# coracao.net
KiCad netlist of a schematic drawn in EAGLE
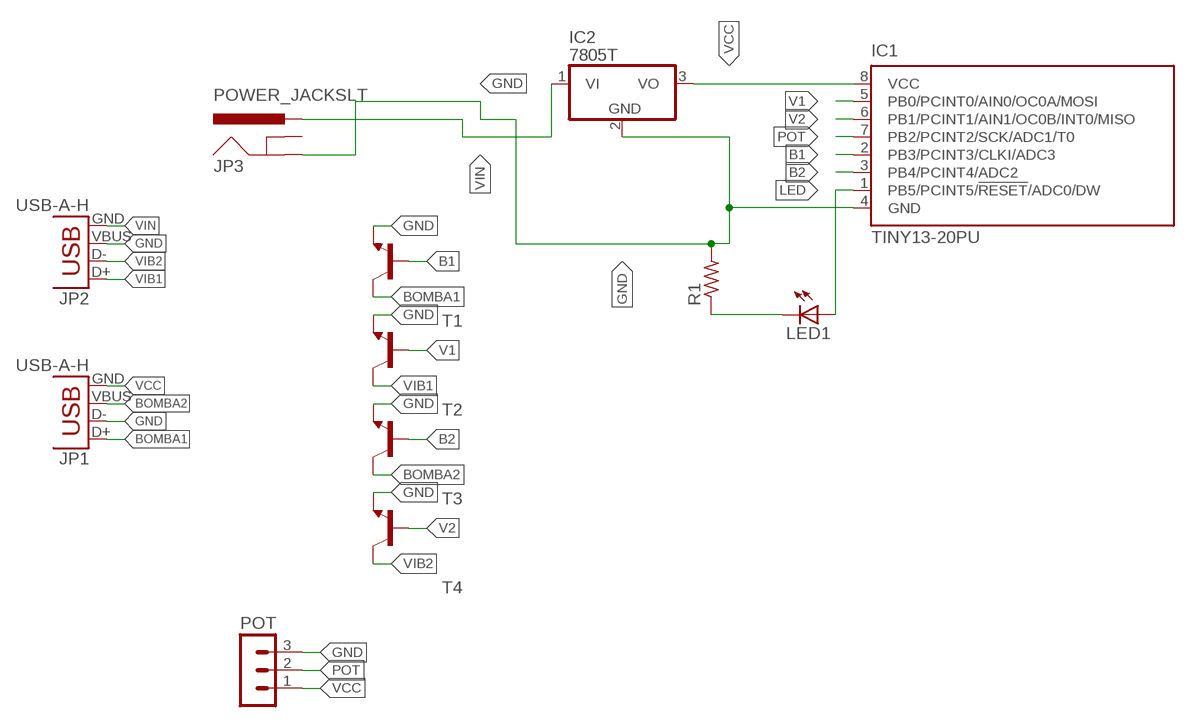
[diagram p0: schematic, sheet 1]

(export (version "E")
  (design (tool "Eeschema 10.0.6"))
  (components
    (comp (ref "IC1")
      (value "TINY13-20PU")
      (footprint "eagle-import:DIL08")
      (fields (field (name "MPN") "ATTINY13-20PU"))
      (libsource (lib "eagle-import") (part "TINY13PU-20"))
    )
    (comp (ref "IC2")
      (value "7805T")
      (footprint "eagle-import:TO220H")
      (libsource (lib "eagle-import") (part "78T05"))
    )
    (comp (ref "JP1")
      (value "USB-A-H")
      (footprint "eagle-import:USB-A-H")
      (libsource (lib "eagle-import") (part "USB-A-H"))
    )
    (comp (ref "JP2")
      (value "USB-A-H")
      (footprint "eagle-import:USB-A-H")
      (libsource (lib "eagle-import") (part "USB-A-H"))
    )
    (comp (ref "JP3")
      (value "POWER_JACKSLT")
      (footprint "eagle-import:POWER_JACK_SLOT")
      (libsource (lib "eagle-import") (part "POWER_JACKSLT"))
    )
    (comp (ref "LED1")
      (value "LED5MM")
      (footprint "eagle-import:LED5MM")
      (libsource (lib "eagle-import") (part "LED5MM"))
    )
    (comp (ref "POT")
      (value "MA03-1")
      (footprint "eagle-import:MA03-1")
      (libsource (lib "eagle-import") (part "MA03-1"))
    )
    (comp (ref "R1")
      (value "R-US_0207/7")
      (footprint "eagle-import:0207_7")
      (libsource (lib "eagle-import") (part "R-US_0207/7"))
    )
    (comp (ref "T1")
      (value "-NPN-TO220V")
      (footprint "eagle-import:TO220V")
      (libsource (lib "eagle-import") (part "-NPN-TO220V"))
    )
    (comp (ref "T2")
      (value "-NPN-TO220V")
      (footprint "eagle-import:TO220V")
      (libsource (lib "eagle-import") (part "-NPN-TO220V"))
    )
    (comp (ref "T3")
      (value "-NPN-TO220V")
      (footprint "eagle-import:TO220V")
      (libsource (lib "eagle-import") (part "-NPN-TO220V"))
    )
    (comp (ref "T4")
      (value "-NPN-TO220V")
      (footprint "eagle-import:TO220V")
      (libsource (lib "eagle-import") (part "-NPN-TO220V"))
    )
  )
  (nets
    (net (code "1") (name "B1") (class "Default")
      (node (ref "IC1") (pin "2") (pinfunction "PB3/PCINT3/CLKI/ADC3_2") (pintype "bidirectional"))
      (node (ref "T1") (pin "1") (pinfunction "B_1") (pintype "passive"))
    )
    (net (code "2") (name "B2") (class "Default")
      (node (ref "IC1") (pin "3") (pinfunction "PB4/PCINT4/ADC2_3") (pintype "bidirectional"))
      (node (ref "T3") (pin "1") (pinfunction "B_1") (pintype "passive"))
    )
    (net (code "3") (name "BOMBA1") (class "Default")
      (node (ref "JP1") (pin "D+") (pinfunction "D+_D+") (pintype "bidirectional"))
      (node (ref "T1") (pin "2") (pinfunction "C_2") (pintype "passive"))
    )
    (net (code "4") (name "BOMBA2") (class "Default")
      (node (ref "JP1") (pin "VBUS") (pinfunction "VBUS_VBUS") (pintype "bidirectional"))
      (node (ref "T3") (pin "2") (pinfunction "C_2") (pintype "passive"))
    )
    (net (code "5") (name "GND") (class "Default")
      (node (ref "IC1") (pin "4") (pinfunction "GND_4") (pintype "power_in"))
      (node (ref "IC2") (pin "2") (pinfunction "GND_2") (pintype "passive"))
      (node (ref "JP1") (pin "D-") (pinfunction "D-_D-") (pintype "bidirectional"))
      (node (ref "JP2") (pin "VBUS") (pinfunction "VBUS_VBUS") (pintype "bidirectional"))
      (node (ref "JP3") (pin "GND@2") (pinfunction "GND_GND@2") (pintype "bidirectional"))
      (node (ref "POT") (pin "3") (pinfunction "3_3") (pintype "passive"))
      (node (ref "R1") (pin "2") (pinfunction "2_2") (pintype "passive"))
      (node (ref "T1") (pin "3") (pinfunction "E_3") (pintype "passive"))
      (node (ref "T2") (pin "3") (pinfunction "E_3") (pintype "passive"))
      (node (ref "T3") (pin "3") (pinfunction "E_3") (pintype "passive"))
      (node (ref "T4") (pin "3") (pinfunction "E_3") (pintype "passive"))
    )
    (net (code "6") (name "LED") (class "Default")
      (node (ref "IC1") (pin "1") (pinfunction "PB5/PCINT5/~{RESET}/ADC0/DW_1") (pintype "bidirectional"))
      (node (ref "LED1") (pin "A") (pinfunction "A_A") (pintype "passive"))
    )
    (net (code "7") (name "Net-(LED1-C)") (class "Default")
      (node (ref "LED1") (pin "K") (pinfunction "C_K") (pintype "passive"))
      (node (ref "R1") (pin "1") (pinfunction "1_1") (pintype "passive"))
    )
    (net (code "8") (name "POT") (class "Default")
      (node (ref "IC1") (pin "7") (pinfunction "PB2/PCINT2/SCK/ADC1/T0_7") (pintype "bidirectional"))
      (node (ref "POT") (pin "2") (pinfunction "2_2") (pintype "passive"))
    )
    (net (code "9") (name "V1") (class "Default")
      (node (ref "IC1") (pin "5") (pinfunction "PB0/PCINT0/AIN0/OC0A/MOSI_5") (pintype "bidirectional"))
      (node (ref "T2") (pin "1") (pinfunction "B_1") (pintype "passive"))
    )
    (net (code "10") (name "V2") (class "Default")
      (node (ref "IC1") (pin "6") (pinfunction "PB1/PCINT1/AIN1/OC0B/INT0/MISO_6") (pintype "bidirectional"))
      (node (ref "T4") (pin "1") (pinfunction "B_1") (pintype "passive"))
    )
    (net (code "11") (name "VCC") (class "Default")
      (node (ref "IC1") (pin "8") (pinfunction "VCC_8") (pintype "power_in"))
      (node (ref "IC2") (pin "3") (pinfunction "VO_3") (pintype "passive"))
      (node (ref "JP1") (pin "GND") (pinfunction "GND_GND") (pintype "bidirectional"))
      (node (ref "POT") (pin "1") (pinfunction "1_1") (pintype "passive"))
    )
    (net (code "12") (name "VIB1") (class "Default")
      (node (ref "JP2") (pin "D+") (pinfunction "D+_D+") (pintype "bidirectional"))
      (node (ref "T2") (pin "2") (pinfunction "C_2") (pintype "passive"))
    )
    (net (code "13") (name "VIB2") (class "Default")
      (node (ref "JP2") (pin "D-") (pinfunction "D-_D-") (pintype "bidirectional"))
      (node (ref "T4") (pin "2") (pinfunction "C_2") (pintype "passive"))
    )
    (net (code "14") (name "VIN") (class "Default")
      (node (ref "IC2") (pin "1") (pinfunction "VI_1") (pintype "input"))
      (node (ref "JP2") (pin "GND") (pinfunction "GND_GND") (pintype "bidirectional"))
      (node (ref "JP3") (pin "PWR") (pinfunction "PWR_PWR") (pintype "bidirectional"))
    )
    (net (code "15") (name "unconnected-(JP3-GNDBREAK-PadGND@1)") (class "Default")
      (node (ref "JP3") (pin "GND@1") (pinfunction "GNDBREAK_GND@1") (pintype "bidirectional"))
    )
  )
)
